# Full-Bridge_Converter.net
KiCad netlist of a schematic drawn in Altium Designer
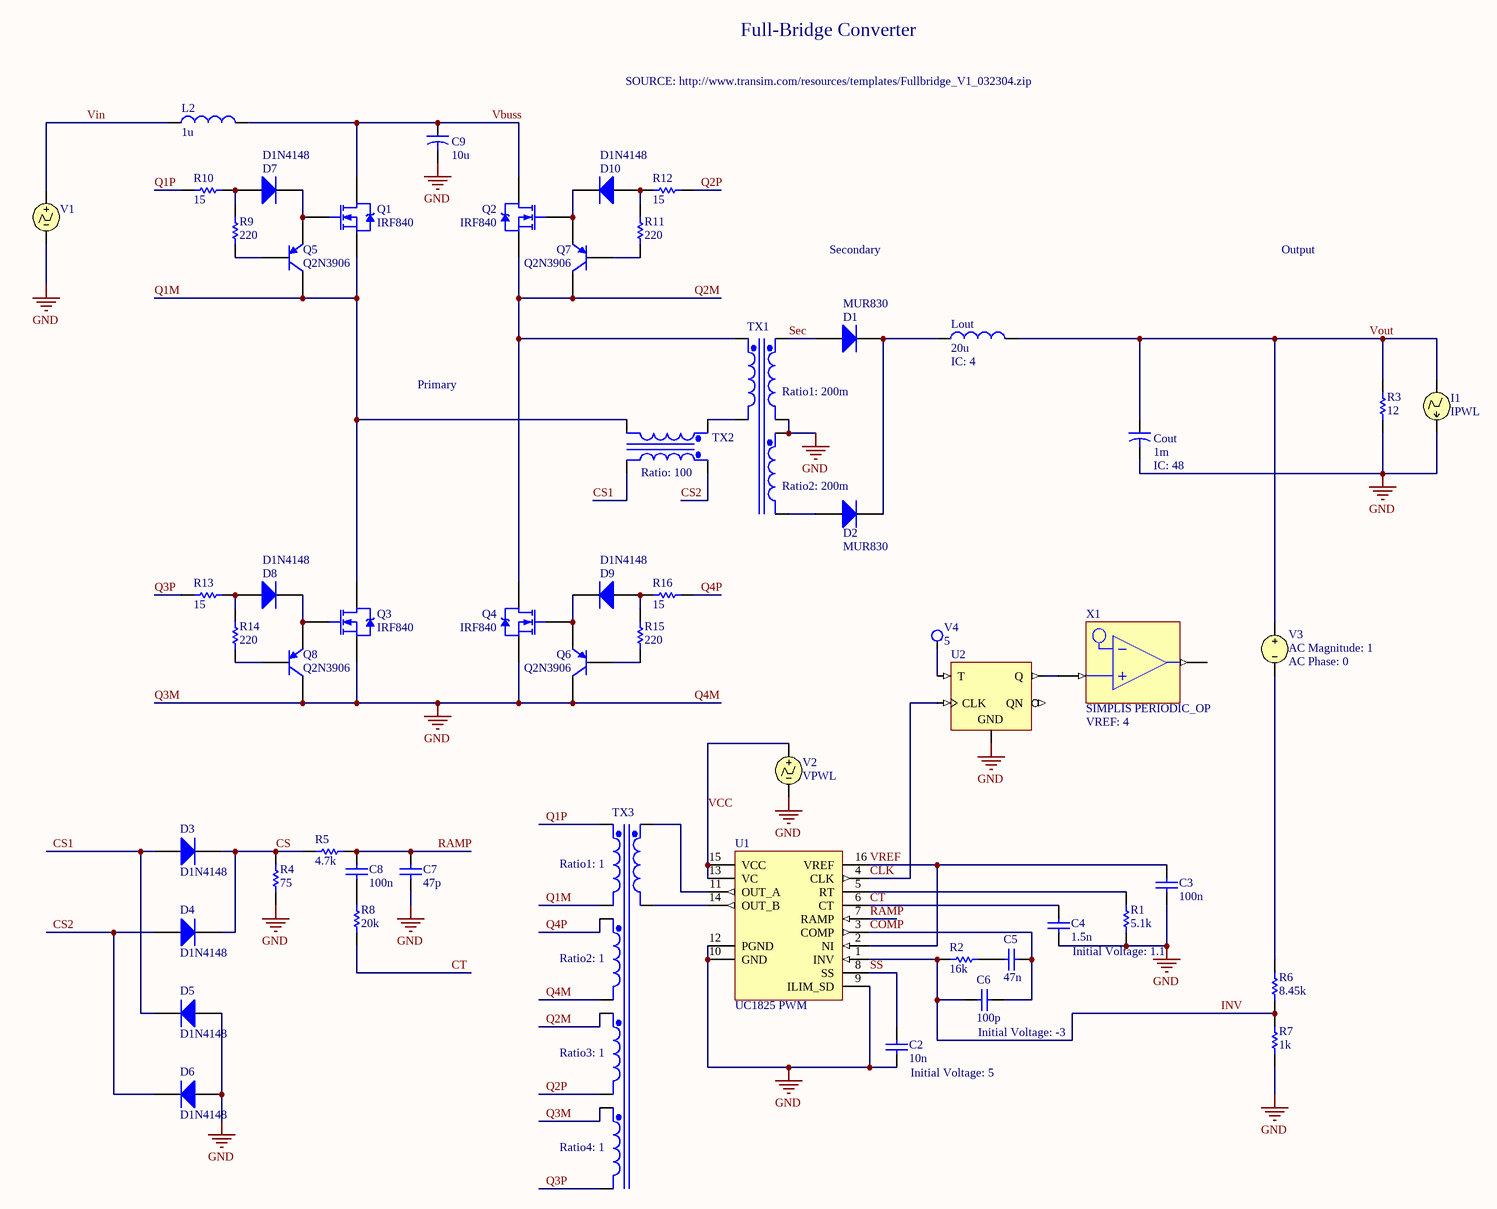
[diagram p0: Full-Bridge Converter.SchDoc]

(export (version "E")
  (design (tool "Eeschema 10.0.6"))
  (components
    (comp (ref "C2")
      (value "10n")
      (footprint "RAD-0.3")
      (description "Capacitor")
      (fields
        (field (name "INITIAL VOLTAGE") "5")
        (field (name "Comment") "Cap")
        (field (name "PUBLISHER") "Altium Limited")
      )
      (libsource (lib "Miscellaneous Devices") (part "Cap"))
    )
    (comp (ref "C3")
      (value "100n")
      (footprint "RAD-0.3")
      (description "Capacitor")
      (fields (field (name "Comment") "Cap") (field (name "PUBLISHER") "Altium Limited"))
      (libsource (lib "Miscellaneous Devices") (part "Cap"))
    )
    (comp (ref "C4")
      (value "1.5n")
      (footprint "RAD-0.3")
      (description "Capacitor")
      (fields
        (field (name "INITIAL VOLTAGE") "1.1")
        (field (name "Comment") "Cap")
        (field (name "PUBLISHER") "Altium Limited")
      )
      (libsource (lib "Miscellaneous Devices") (part "Cap"))
    )
    (comp (ref "C5")
      (value "47n")
      (footprint "RAD-0.3")
      (description "Capacitor")
      (fields (field (name "Comment") "Cap") (field (name "PUBLISHER") "Altium Limited"))
      (libsource (lib "Miscellaneous Devices") (part "Cap"))
    )
    (comp (ref "C6")
      (value "100p")
      (footprint "RAD-0.3")
      (description "Capacitor")
      (fields
        (field (name "INITIAL VOLTAGE") "-3")
        (field (name "Comment") "Cap")
        (field (name "PUBLISHER") "Altium Limited")
      )
      (libsource (lib "Miscellaneous Devices") (part "Cap"))
    )
    (comp (ref "C7")
      (value "47p")
      (footprint "RAD-0.3")
      (description "Capacitor")
      (fields (field (name "Comment") "Cap") (field (name "PUBLISHER") "Altium Limited"))
      (libsource (lib "Miscellaneous Devices") (part "Cap"))
    )
    (comp (ref "C8")
      (value "100n")
      (footprint "RAD-0.3")
      (description "Capacitor")
      (fields (field (name "Comment") "Cap") (field (name "PUBLISHER") "Altium Limited"))
      (libsource (lib "Miscellaneous Devices") (part "Cap"))
    )
    (comp (ref "C9")
      (value "Cap Elec (L1-3)")
      (footprint "CAPR5-4X5")
      (description "Electrolytic Capacitor (Levels 1-3)")
      (fields (field (name "CC") "10u") (field (name "PUBLISHER") "Altium Limited"))
      (libsource (lib "SIMetrix Devices") (part "Cap Elec (L1-3)"))
    )
    (comp (ref "Cout")
      (value "Cap Elec (L1-3)")
      (footprint "CAPR5-4X5")
      (description "Electrolytic Capacitor (Levels 1-3)")
      (fields (field (name "IC") "48") (field (name "CC") "1m") (field (name "PUBLISHER") "Altium Limited"))
      (libsource (lib "SIMetrix Devices") (part "Cap Elec (L1-3)"))
    )
    (comp (ref "D1")
      (value "MUR830")
      (footprint "SMC")
      (description "General Purpose Fast Rectifier")
      (libsource (lib "SIMetrix Devices") (part "MUR830"))
    )
    (comp (ref "D2")
      (value "MUR830")
      (footprint "SMC")
      (description "General Purpose Fast Rectifier")
      (libsource (lib "SIMetrix Devices") (part "MUR830"))
    )
    (comp (ref "D3")
      (value "D1N4148")
      (footprint "DO-35")
      (description "High Conductance Fast Diode")
      (fields (field (name "PUBLISHER") "Altium Limited"))
      (libsource (lib "SIMetrix Devices") (part "D1N4148"))
    )
    (comp (ref "D4")
      (value "D1N4148")
      (footprint "DO-35")
      (description "High Conductance Fast Diode")
      (fields (field (name "PUBLISHER") "Altium Limited"))
      (libsource (lib "SIMetrix Devices") (part "D1N4148"))
    )
    (comp (ref "D5")
      (value "D1N4148")
      (footprint "DO-35")
      (description "High Conductance Fast Diode")
      (fields (field (name "PUBLISHER") "Altium Limited"))
      (libsource (lib "SIMetrix Devices") (part "D1N4148"))
    )
    (comp (ref "D6")
      (value "D1N4148")
      (footprint "DO-35")
      (description "High Conductance Fast Diode")
      (fields (field (name "PUBLISHER") "Altium Limited"))
      (libsource (lib "SIMetrix Devices") (part "D1N4148"))
    )
    (comp (ref "D7")
      (value "D1N4148")
      (footprint "DO-35")
      (description "High Conductance Fast Diode")
      (fields (field (name "PUBLISHER") "Altium Limited"))
      (libsource (lib "SIMetrix Devices") (part "D1N4148"))
    )
    (comp (ref "D8")
      (value "D1N4148")
      (footprint "DO-35")
      (description "High Conductance Fast Diode")
      (fields (field (name "PUBLISHER") "Altium Limited"))
      (libsource (lib "SIMetrix Devices") (part "D1N4148"))
    )
    (comp (ref "D9")
      (value "D1N4148")
      (footprint "DO-35")
      (description "High Conductance Fast Diode")
      (fields (field (name "PUBLISHER") "Altium Limited"))
      (libsource (lib "SIMetrix Devices") (part "D1N4148"))
    )
    (comp (ref "D10")
      (value "D1N4148")
      (footprint "DO-35")
      (description "High Conductance Fast Diode")
      (fields (field (name "PUBLISHER") "Altium Limited"))
      (libsource (lib "SIMetrix Devices") (part "D1N4148"))
    )
    (comp (ref "I1")
      (value "IPWL")
      (footprint "HDR1X2H")
      (description "Piecewise Linear Current Source")
      (fields (field (name "PUBLISHER") "Altium Limited"))
      (libsource (lib "Simulation Sources") (part "IPWL"))
    )
    (comp (ref "L2")
      (value "1u")
      (footprint "0402-A")
      (description "Lossy Inductor")
      (fields (field (name "PUBLISHER") "Altium Limited"))
      (libsource (lib "SIMetrix Devices") (part "Inductor (Lossy)"))
    )
    (comp (ref "Lout")
      (value "20u")
      (footprint "0402-A")
      (description "Lossy Inductor")
      (fields (field (name "IC") "4") (field (name "PUBLISHER") "Altium Limited"))
      (libsource (lib "SIMetrix Devices") (part "Inductor (Lossy)"))
    )
    (comp (ref "Q1")
      (value "IRF840")
      (footprint "TO-220AB")
      (description "HEXFET N-Channel Power MOSFET")
      (fields (field (name "PUBLISHER") "Altium Limited"))
      (libsource (lib "SIMetrix Devices") (part "IRF840"))
    )
    (comp (ref "Q2")
      (value "IRF840")
      (footprint "TO-220AB")
      (description "HEXFET N-Channel Power MOSFET")
      (fields (field (name "PUBLISHER") "Altium Limited"))
      (libsource (lib "SIMetrix Devices") (part "IRF840"))
    )
    (comp (ref "Q3")
      (value "IRF840")
      (footprint "TO-220AB")
      (description "HEXFET N-Channel Power MOSFET")
      (fields (field (name "PUBLISHER") "Altium Limited"))
      (libsource (lib "SIMetrix Devices") (part "IRF840"))
    )
    (comp (ref "Q4")
      (value "IRF840")
      (footprint "TO-220AB")
      (description "HEXFET N-Channel Power MOSFET")
      (fields (field (name "PUBLISHER") "Altium Limited"))
      (libsource (lib "SIMetrix Devices") (part "IRF840"))
    )
    (comp (ref "Q5")
      (value "Q2N3906")
      (footprint "TO-92A")
      (description "PNP General Purpose Amplifier")
      (fields (field (name "PUBLISHER") "Altium Limited"))
      (libsource (lib "SIMetrix Devices") (part "Q2N3906"))
    )
    (comp (ref "Q6")
      (value "Q2N3906")
      (footprint "TO-92A")
      (description "PNP General Purpose Amplifier")
      (fields (field (name "PUBLISHER") "Altium Limited"))
      (libsource (lib "SIMetrix Devices") (part "Q2N3906"))
    )
    (comp (ref "Q7")
      (value "Q2N3906")
      (footprint "TO-92A")
      (description "PNP General Purpose Amplifier")
      (fields (field (name "PUBLISHER") "Altium Limited"))
      (libsource (lib "SIMetrix Devices") (part "Q2N3906"))
    )
    (comp (ref "Q8")
      (value "Q2N3906")
      (footprint "TO-92A")
      (description "PNP General Purpose Amplifier")
      (fields (field (name "PUBLISHER") "Altium Limited"))
      (libsource (lib "SIMetrix Devices") (part "Q2N3906"))
    )
    (comp (ref "R1")
      (value "5.1k")
      (footprint "AXIAL-0.3")
      (description "Resistor")
      (fields (field (name "Comment") "Res1") (field (name "PUBLISHER") "Altium Limited"))
      (libsource (lib "Miscellaneous Devices") (part "Res1"))
    )
    (comp (ref "R2")
      (value "16k")
      (footprint "AXIAL-0.3")
      (description "Resistor")
      (fields (field (name "Comment") "Res1") (field (name "PUBLISHER") "Altium Limited"))
      (libsource (lib "Miscellaneous Devices") (part "Res1"))
    )
    (comp (ref "R3")
      (value "12")
      (footprint "AXIAL-0.3")
      (description "Resistor")
      (fields (field (name "Comment") "Res1") (field (name "PUBLISHER") "Altium Limited"))
      (libsource (lib "Miscellaneous Devices") (part "Res1"))
    )
    (comp (ref "R4")
      (value "75")
      (footprint "AXIAL-0.3")
      (description "Resistor")
      (fields (field (name "Comment") "Res1") (field (name "PUBLISHER") "Altium Limited"))
      (libsource (lib "Miscellaneous Devices") (part "Res1"))
    )
    (comp (ref "R5")
      (value "4.7k")
      (footprint "AXIAL-0.3")
      (description "Resistor")
      (fields (field (name "Comment") "Res1") (field (name "PUBLISHER") "Altium Limited"))
      (libsource (lib "Miscellaneous Devices") (part "Res1"))
    )
    (comp (ref "R6")
      (value "8.45k")
      (footprint "AXIAL-0.3")
      (description "Resistor")
      (fields (field (name "Comment") "Res1") (field (name "PUBLISHER") "Altium Limited"))
      (libsource (lib "Miscellaneous Devices") (part "Res1"))
    )
    (comp (ref "R7")
      (value "1k")
      (footprint "AXIAL-0.3")
      (description "Resistor")
      (fields (field (name "Comment") "Res1") (field (name "PUBLISHER") "Altium Limited"))
      (libsource (lib "Miscellaneous Devices") (part "Res1"))
    )
    (comp (ref "R8")
      (value "20k")
      (footprint "AXIAL-0.3")
      (description "Resistor")
      (fields (field (name "Comment") "Res1") (field (name "PUBLISHER") "Altium Limited"))
      (libsource (lib "Miscellaneous Devices") (part "Res1"))
    )
    (comp (ref "R9")
      (value "220")
      (footprint "AXIAL-0.3")
      (description "Resistor")
      (fields (field (name "Comment") "Res1") (field (name "PUBLISHER") "Altium Limited"))
      (libsource (lib "Miscellaneous Devices") (part "Res1"))
    )
    (comp (ref "R10")
      (value "15")
      (footprint "AXIAL-0.3")
      (description "Resistor")
      (fields (field (name "Comment") "Res1") (field (name "PUBLISHER") "Altium Limited"))
      (libsource (lib "Miscellaneous Devices") (part "Res1"))
    )
    (comp (ref "R11")
      (value "220")
      (footprint "AXIAL-0.3")
      (description "Resistor")
      (fields (field (name "Comment") "Res1") (field (name "PUBLISHER") "Altium Limited"))
      (libsource (lib "Miscellaneous Devices") (part "Res1"))
    )
    (comp (ref "R12")
      (value "15")
      (footprint "AXIAL-0.3")
      (description "Resistor")
      (fields (field (name "Comment") "Res1") (field (name "PUBLISHER") "Altium Limited"))
      (libsource (lib "Miscellaneous Devices") (part "Res1"))
    )
    (comp (ref "R13")
      (value "15")
      (footprint "AXIAL-0.3")
      (description "Resistor")
      (fields (field (name "Comment") "Res1") (field (name "PUBLISHER") "Altium Limited"))
      (libsource (lib "Miscellaneous Devices") (part "Res1"))
    )
    (comp (ref "R14")
      (value "220")
      (footprint "AXIAL-0.3")
      (description "Resistor")
      (fields (field (name "Comment") "Res1") (field (name "PUBLISHER") "Altium Limited"))
      (libsource (lib "Miscellaneous Devices") (part "Res1"))
    )
    (comp (ref "R15")
      (value "220")
      (footprint "AXIAL-0.3")
      (description "Resistor")
      (fields (field (name "Comment") "Res1") (field (name "PUBLISHER") "Altium Limited"))
      (libsource (lib "Miscellaneous Devices") (part "Res1"))
    )
    (comp (ref "R16")
      (value "15")
      (footprint "AXIAL-0.3")
      (description "Resistor")
      (fields (field (name "Comment") "Res1") (field (name "PUBLISHER") "Altium Limited"))
      (libsource (lib "Miscellaneous Devices") (part "Res1"))
    )
    (comp (ref "TX1")
      (value "Trans3 Simpl")
      (footprint "TRF_6")
      (description "Three-winding Transformer (Simplified Model)")
      (fields
        (field (name "RATIO1") "200m")
        (field (name "RATIO2") "200m")
        (field (name "PUBLISHER") "Altium Limited")
      )
      (libsource (lib "SIMetrix Devices") (part "Trans3 Simpl"))
    )
    (comp (ref "TX2")
      (value "Trans Simpl")
      (footprint "TRF_4")
      (description "Transformer (Simplified Model)")
      (fields (field (name "RATIO") "100") (field (name "PUBLISHER") "Altium Limited"))
      (libsource (lib "SIMetrix Devices") (part "Trans Simpl"))
    )
    (comp (ref "TX3")
      (value "Trans5 Simpl")
      (footprint "TRF_10")
      (description "Five-winding Transformer (Simplified Model)")
      (fields
        (field (name "RATIO1") "1")
        (field (name "RATIO2") "1")
        (field (name "RATIO3") "1")
        (field (name "RATIO4") "1")
        (field (name "PUBLISHER") "Altium Limited")
      )
      (libsource (lib "SIMetrix Devices") (part "Trans5 Simpl"))
    )
    (comp (ref "U1")
      (value "UC1825 PWM")
      (description "High-Speed PWM Controller")
      (libsource (lib "SIMetrix Devices") (part "UC1825"))
    )
    (comp (ref "U2")
      (value "SIMPLIS CLK_TFF")
      (description "Toggle Flip-Flop")
      (libsource (lib "SIMPLIS Devices") (part "SIMPLIS CLK_TFF"))
    )
    (comp (ref "V1")
      (value "VPWL")
      (footprint "HDR1X2H")
      (description "Piecewise Linear Voltage Source")
      (fields (field (name "PUBLISHER") "Altium Limited"))
      (libsource (lib "Simulation Sources") (part "VPWL"))
    )
    (comp (ref "V2")
      (value "VPWL")
      (footprint "HDR1X2H")
      (description "Piecewise Linear Voltage Source")
      (fields (field (name "PUBLISHER") "Altium Limited"))
      (libsource (lib "Simulation Sources") (part "VPWL"))
    )
    (comp (ref "V3")
      (value "VSRC")
      (description "Voltage Source")
      (fields
        (field (name "AC MAGNITUDE") "1")
        (field (name "AC PHASE") "0")
        (field (name "PUBLISHER") "Altium Limited")
      )
      (libsource (lib "Simulation Sources") (part "VSRC"))
    )
    (comp (ref "V4")
      (value "5")
      (description "Voltage Source")
      (fields (field (name "Comment") "VSRC2") (field (name "PUBLISHER") "Altium Limited"))
      (libsource (lib "Simulation Sources") (part "VSRC2"))
    )
    (comp (ref "X1")
      (value "SIMPLIS PERIODIC_OP")
      (description "Periodic Operating Point Analysis Trigger")
      (fields (field (name "VREF") "4") (field (name "PUBLISHER") "Altium Limited"))
      (libsource (lib "SIMPLIS Devices") (part "SIMPLIS PERIODIC_OP"))
    )
  )
  (nets
    (net (code "1") (name "/CLK") (class "Default")
      (node (ref "U1") (pin "4") (pinfunction "CLK_4") (pintype "output"))
      (node (ref "U2") (pin "191") (pinfunction "CLK_191") (pintype "input"))
    )
    (net (code "2") (name "/COMP") (class "Default")
      (node (ref "C5") (pin "1") (pinfunction "1_1") (pintype "passive"))
      (node (ref "C6") (pin "1") (pinfunction "1_1") (pintype "passive"))
      (node (ref "U1") (pin "3") (pinfunction "COMP_3") (pintype "output"))
    )
    (net (code "3") (name "/CS") (class "Default")
      (node (ref "D3") (pin "2") (pinfunction "K_2") (pintype "passive"))
      (node (ref "D4") (pin "2") (pinfunction "K_2") (pintype "passive"))
      (node (ref "R4") (pin "1") (pinfunction "1_1") (pintype "passive"))
      (node (ref "R5") (pin "1") (pinfunction "1_1") (pintype "passive"))
    )
    (net (code "4") (name "/CS1") (class "Default")
      (node (ref "D3") (pin "1") (pinfunction "A_1") (pintype "passive"))
      (node (ref "D5") (pin "2") (pinfunction "K_2") (pintype "passive"))
      (node (ref "TX2") (pin "4") (pinfunction "Sec-_4") (pintype "passive"))
    )
    (net (code "5") (name "/CS2") (class "Default")
      (node (ref "D4") (pin "1") (pinfunction "A_1") (pintype "passive"))
      (node (ref "D6") (pin "2") (pinfunction "K_2") (pintype "passive"))
      (node (ref "TX2") (pin "3") (pinfunction "Sec+_3") (pintype "passive"))
    )
    (net (code "6") (name "/CT") (class "Default")
      (node (ref "C4") (pin "1") (pinfunction "1_1") (pintype "passive"))
      (node (ref "R8") (pin "2") (pinfunction "2_2") (pintype "passive"))
      (node (ref "U1") (pin "6") (pinfunction "CT_6") (pintype "passive"))
    )
    (net (code "7") (name "/INV") (class "Default")
      (node (ref "C6") (pin "2") (pinfunction "2_2") (pintype "passive"))
      (node (ref "R2") (pin "2") (pinfunction "2_2") (pintype "passive"))
      (node (ref "R6") (pin "2") (pinfunction "2_2") (pintype "passive"))
      (node (ref "R7") (pin "1") (pinfunction "1_1") (pintype "passive"))
      (node (ref "U1") (pin "1") (pinfunction "INV_1") (pintype "input"))
    )
    (net (code "8") (name "/Q1M") (class "Default")
      (node (ref "Q1") (pin "3") (pinfunction "S_3") (pintype "passive"))
      (node (ref "Q3") (pin "2") (pinfunction "D_2") (pintype "passive"))
      (node (ref "Q5") (pin "3") (pinfunction "C_3") (pintype "passive"))
      (node (ref "TX2") (pin "2") (pinfunction "Pri-_2") (pintype "passive"))
      (node (ref "TX3") (pin "4") (pinfunction "Sec1-_4") (pintype "passive"))
    )
    (net (code "9") (name "/Q1P") (class "Default")
      (node (ref "R10") (pin "1") (pinfunction "1_1") (pintype "passive"))
      (node (ref "TX3") (pin "3") (pinfunction "Sec1+_3") (pintype "passive"))
    )
    (net (code "10") (name "/Q2M") (class "Default")
      (node (ref "Q2") (pin "3") (pinfunction "S_3") (pintype "passive"))
      (node (ref "Q4") (pin "2") (pinfunction "D_2") (pintype "passive"))
      (node (ref "Q7") (pin "3") (pinfunction "C_3") (pintype "passive"))
      (node (ref "TX1") (pin "1") (pinfunction "Pri+_1") (pintype "passive"))
      (node (ref "TX3") (pin "7") (pinfunction "Sec3+_7") (pintype "passive"))
    )
    (net (code "11") (name "/Q2P") (class "Default")
      (node (ref "R12") (pin "2") (pinfunction "2_2") (pintype "passive"))
      (node (ref "TX3") (pin "8") (pinfunction "Sec3-_8") (pintype "passive"))
    )
    (net (code "12") (name "/Q3P") (class "Default")
      (node (ref "R13") (pin "1") (pinfunction "1_1") (pintype "passive"))
      (node (ref "TX3") (pin "10") (pinfunction "Sec4-_10") (pintype "passive"))
    )
    (net (code "13") (name "/Q4P") (class "Default")
      (node (ref "R16") (pin "2") (pinfunction "2_2") (pintype "passive"))
      (node (ref "TX3") (pin "5") (pinfunction "Sec2+_5") (pintype "passive"))
    )
    (net (code "14") (name "/RAMP") (class "Default")
      (node (ref "C7") (pin "1") (pinfunction "1_1") (pintype "passive"))
      (node (ref "C8") (pin "1") (pinfunction "1_1") (pintype "passive"))
      (node (ref "R5") (pin "2") (pinfunction "2_2") (pintype "passive"))
      (node (ref "U1") (pin "7") (pinfunction "RAMP_7") (pintype "input"))
    )
    (net (code "15") (name "/SS") (class "Default")
      (node (ref "C2") (pin "1") (pinfunction "1_1") (pintype "passive"))
      (node (ref "U1") (pin "8") (pinfunction "SS_8") (pintype "power_in"))
    )
    (net (code "16") (name "/Sec") (class "Default")
      (node (ref "D1") (pin "1") (pinfunction "A_1") (pintype "passive"))
      (node (ref "TX1") (pin "3") (pinfunction "Sec1+_3") (pintype "passive"))
    )
    (net (code "17") (name "/VCC") (class "Default")
      (node (ref "U1") (pin "13") (pinfunction "VC_13") (pintype "power_in"))
      (node (ref "U1") (pin "15") (pinfunction "VCC_15") (pintype "passive"))
      (node (ref "V2") (pin "1") (pinfunction "1_1") (pintype "passive"))
    )
    (net (code "18") (name "/VREF") (class "Default")
      (node (ref "C3") (pin "1") (pinfunction "1_1") (pintype "passive"))
      (node (ref "U1") (pin "16") (pinfunction "VREF_16") (pintype "power_in"))
      (node (ref "U1") (pin "2") (pinfunction "NI_2") (pintype "input"))
    )
    (net (code "19") (name "/Vbuss") (class "Default")
      (node (ref "C9") (pin "1") (pinfunction "1_1") (pintype "passive"))
      (node (ref "L2") (pin "2") (pinfunction "2_2") (pintype "passive"))
      (node (ref "Q1") (pin "2") (pinfunction "D_2") (pintype "passive"))
      (node (ref "Q2") (pin "2") (pinfunction "D_2") (pintype "passive"))
    )
    (net (code "20") (name "/Vin") (class "Default")
      (node (ref "L2") (pin "1") (pinfunction "1_1") (pintype "passive"))
      (node (ref "V1") (pin "1") (pinfunction "1_1") (pintype "passive"))
    )
    (net (code "21") (name "/Vout") (class "Default")
      (node (ref "Cout") (pin "1") (pinfunction "1_1") (pintype "passive"))
      (node (ref "I1") (pin "1") (pinfunction "1_1") (pintype "passive"))
      (node (ref "Lout") (pin "2") (pinfunction "2_2") (pintype "passive"))
      (node (ref "R3") (pin "1") (pinfunction "1_1") (pintype "passive"))
      (node (ref "V3") (pin "1") (pinfunction "1_1") (pintype "passive"))
    )
    (net (code "22") (name "GND") (class "Default")
      (node (ref "C2") (pin "2") (pinfunction "2_2") (pintype "passive"))
      (node (ref "C3") (pin "2") (pinfunction "2_2") (pintype "passive"))
      (node (ref "C4") (pin "2") (pinfunction "2_2") (pintype "passive"))
      (node (ref "C7") (pin "2") (pinfunction "2_2") (pintype "passive"))
      (node (ref "C9") (pin "2") (pinfunction "2_2") (pintype "passive"))
      (node (ref "Cout") (pin "2") (pinfunction "2_2") (pintype "passive"))
      (node (ref "D5") (pin "1") (pinfunction "A_1") (pintype "passive"))
      (node (ref "D6") (pin "1") (pinfunction "A_1") (pintype "passive"))
      (node (ref "I1") (pin "2") (pinfunction "2_2") (pintype "passive"))
      (node (ref "Q3") (pin "3") (pinfunction "S_3") (pintype "passive"))
      (node (ref "Q4") (pin "3") (pinfunction "S_3") (pintype "passive"))
      (node (ref "Q6") (pin "3") (pinfunction "C_3") (pintype "passive"))
      (node (ref "Q8") (pin "3") (pinfunction "C_3") (pintype "passive"))
      (node (ref "R1") (pin "2") (pinfunction "2_2") (pintype "passive"))
      (node (ref "R3") (pin "2") (pinfunction "2_2") (pintype "passive"))
      (node (ref "R4") (pin "2") (pinfunction "2_2") (pintype "passive"))
      (node (ref "R7") (pin "2") (pinfunction "2_2") (pintype "passive"))
      (node (ref "TX1") (pin "4") (pinfunction "Sec1-_4") (pintype "passive"))
      (node (ref "TX1") (pin "5") (pinfunction "Sec2+_5") (pintype "passive"))
      (node (ref "TX3") (pin "6") (pinfunction "Sec2-_6") (pintype "passive"))
      (node (ref "TX3") (pin "9") (pinfunction "Sec4+_9") (pintype "passive"))
      (node (ref "U1") (pin "10") (pinfunction "GND_10") (pintype "passive"))
      (node (ref "U1") (pin "12") (pinfunction "PGND_12") (pintype "passive"))
      (node (ref "U1") (pin "9") (pinfunction "ILIM_SD_9") (pintype "passive"))
      (node (ref "U2") (pin "100") (pinfunction "GND_100") (pintype "passive"))
      (node (ref "V1") (pin "2") (pinfunction "2_2") (pintype "passive"))
      (node (ref "V2") (pin "2") (pinfunction "2_2") (pintype "passive"))
    )
    (net (code "23") (name "Net-(C5-Pad2)") (class "Default")
      (node (ref "C5") (pin "2") (pinfunction "2_2") (pintype "passive"))
      (node (ref "R2") (pin "1") (pinfunction "1_1") (pintype "passive"))
    )
    (net (code "24") (name "Net-(C8-Pad2)") (class "Default")
      (node (ref "C8") (pin "2") (pinfunction "2_2") (pintype "passive"))
      (node (ref "R8") (pin "1") (pinfunction "1_1") (pintype "passive"))
    )
    (net (code "25") (name "Net-(D1-K)") (class "Default")
      (node (ref "D1") (pin "2") (pinfunction "K_2") (pintype "passive"))
      (node (ref "D2") (pin "2") (pinfunction "K_2") (pintype "passive"))
      (node (ref "Lout") (pin "1") (pinfunction "1_1") (pintype "passive"))
    )
    (net (code "26") (name "Net-(D2-A)") (class "Default")
      (node (ref "D2") (pin "1") (pinfunction "A_1") (pintype "passive"))
      (node (ref "TX1") (pin "6") (pinfunction "Sec2-_6") (pintype "passive"))
    )
    (net (code "27") (name "Net-(D7-A)") (class "Default")
      (node (ref "D7") (pin "1") (pinfunction "A_1") (pintype "passive"))
      (node (ref "R10") (pin "2") (pinfunction "2_2") (pintype "passive"))
      (node (ref "R9") (pin "1") (pinfunction "1_1") (pintype "passive"))
    )
    (net (code "28") (name "Net-(D7-K)") (class "Default")
      (node (ref "D7") (pin "2") (pinfunction "K_2") (pintype "passive"))
      (node (ref "Q1") (pin "1") (pinfunction "G_1") (pintype "passive"))
      (node (ref "Q5") (pin "1") (pinfunction "E_1") (pintype "passive"))
    )
    (net (code "29") (name "Net-(D8-A)") (class "Default")
      (node (ref "D8") (pin "1") (pinfunction "A_1") (pintype "passive"))
      (node (ref "R13") (pin "2") (pinfunction "2_2") (pintype "passive"))
      (node (ref "R14") (pin "1") (pinfunction "1_1") (pintype "passive"))
    )
    (net (code "30") (name "Net-(D8-K)") (class "Default")
      (node (ref "D8") (pin "2") (pinfunction "K_2") (pintype "passive"))
      (node (ref "Q3") (pin "1") (pinfunction "G_1") (pintype "passive"))
      (node (ref "Q8") (pin "1") (pinfunction "E_1") (pintype "passive"))
    )
    (net (code "31") (name "Net-(D9-A)") (class "Default")
      (node (ref "D9") (pin "1") (pinfunction "A_1") (pintype "passive"))
      (node (ref "R15") (pin "1") (pinfunction "1_1") (pintype "passive"))
      (node (ref "R16") (pin "1") (pinfunction "1_1") (pintype "passive"))
    )
    (net (code "32") (name "Net-(D9-K)") (class "Default")
      (node (ref "D9") (pin "2") (pinfunction "K_2") (pintype "passive"))
      (node (ref "Q4") (pin "1") (pinfunction "G_1") (pintype "passive"))
      (node (ref "Q6") (pin "1") (pinfunction "E_1") (pintype "passive"))
    )
    (net (code "33") (name "Net-(D10-A)") (class "Default")
      (node (ref "D10") (pin "1") (pinfunction "A_1") (pintype "passive"))
      (node (ref "R11") (pin "1") (pinfunction "1_1") (pintype "passive"))
      (node (ref "R12") (pin "1") (pinfunction "1_1") (pintype "passive"))
    )
    (net (code "34") (name "Net-(D10-K)") (class "Default")
      (node (ref "D10") (pin "2") (pinfunction "K_2") (pintype "passive"))
      (node (ref "Q2") (pin "1") (pinfunction "G_1") (pintype "passive"))
      (node (ref "Q7") (pin "1") (pinfunction "E_1") (pintype "passive"))
    )
    (net (code "35") (name "Net-(Q5-B)") (class "Default")
      (node (ref "Q5") (pin "2") (pinfunction "B_2") (pintype "passive"))
      (node (ref "R9") (pin "2") (pinfunction "2_2") (pintype "passive"))
    )
    (net (code "36") (name "Net-(Q6-B)") (class "Default")
      (node (ref "Q6") (pin "2") (pinfunction "B_2") (pintype "passive"))
      (node (ref "R15") (pin "2") (pinfunction "2_2") (pintype "passive"))
    )
    (net (code "37") (name "Net-(Q7-B)") (class "Default")
      (node (ref "Q7") (pin "2") (pinfunction "B_2") (pintype "passive"))
      (node (ref "R11") (pin "2") (pinfunction "2_2") (pintype "passive"))
    )
    (net (code "38") (name "Net-(Q8-B)") (class "Default")
      (node (ref "Q8") (pin "2") (pinfunction "B_2") (pintype "passive"))
      (node (ref "R14") (pin "2") (pinfunction "2_2") (pintype "passive"))
    )
    (net (code "39") (name "Net-(R6-Pad1)") (class "Default")
      (node (ref "R6") (pin "1") (pinfunction "1_1") (pintype "passive"))
      (node (ref "V3") (pin "2") (pinfunction "2_2") (pintype "passive"))
    )
    (net (code "40") (name "Net-(TX1-Pri-)") (class "Default")
      (node (ref "TX1") (pin "2") (pinfunction "Pri-_2") (pintype "passive"))
      (node (ref "TX2") (pin "1") (pinfunction "Pri+_1") (pintype "passive"))
    )
    (net (code "41") (name "Net-(TX3-Pri+)") (class "Default")
      (node (ref "TX3") (pin "1") (pinfunction "Pri+_1") (pintype "passive"))
      (node (ref "U1") (pin "11") (pinfunction "OUT_A_11") (pintype "output"))
    )
    (net (code "42") (name "Net-(TX3-Pri-)") (class "Default")
      (node (ref "TX3") (pin "2") (pinfunction "Pri-_2") (pintype "passive"))
      (node (ref "U1") (pin "14") (pinfunction "OUT_B_14") (pintype "output"))
    )
    (net (code "43") (name "Net-(U1-RT)") (class "Default")
      (node (ref "R1") (pin "1") (pinfunction "1_1") (pintype "passive"))
      (node (ref "U1") (pin "5") (pinfunction "RT_5") (pintype "passive"))
    )
    (net (code "44") (name "Net-(U2-Q)") (class "Default")
      (node (ref "U2") (pin "201") (pinfunction "Q_201") (pintype "output"))
      (node (ref "X1") (pin "1") (pinfunction "IN_1") (pintype "input"))
    )
    (net (code "45") (name "Net-(U2-T)") (class "Default")
      (node (ref "U2") (pin "101") (pinfunction "T_101") (pintype "input"))
      (node (ref "V4") (pin "1") (pinfunction "1_1") (pintype "passive"))
    )
    (net (code "46") (name "unconnected-(U2-QN-Pad202)") (class "Default")
      (node (ref "U2") (pin "202") (pinfunction "QN_202") (pintype "output"))
    )
    (net (code "47") (name "unconnected-(X1-OUT-Pad3)") (class "Default")
      (node (ref "X1") (pin "3") (pinfunction "OUT_3") (pintype "output"))
    )
  )
)
